# Brelok_MFU.net
KiCad netlist of a schematic drawn in Altium Designer
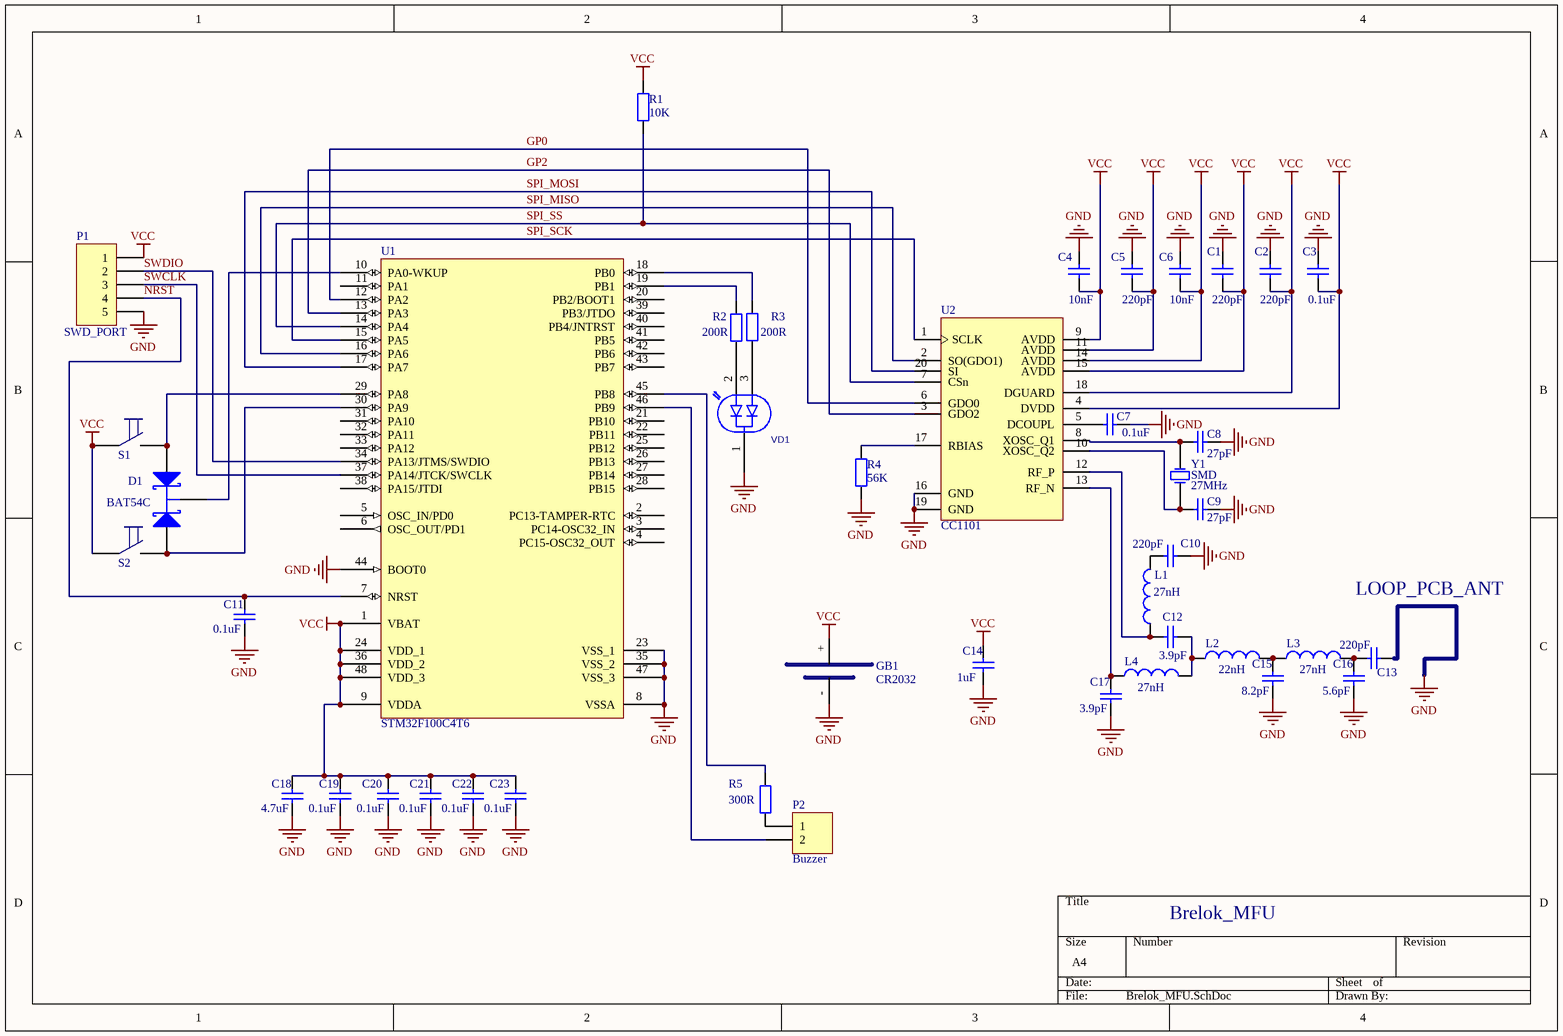
[diagram p0: Brelok_MFU.SchDoc]

(export (version "E")
  (design (tool "Eeschema 10.0.6"))
  (components
    (comp (ref "C1")
      (value "220pF")
      (footprint "C0603")
      (description "Capasitor_SMD_0808/")
      (fields (field (name "Comment") "0805"))
      (libsource (lib "NEW") (part "Capasitor_SMD_0805"))
    )
    (comp (ref "C2")
      (value "220pF")
      (footprint "C0603")
      (description "Capasitor_SMD_0808/")
      (fields (field (name "Comment") "0805"))
      (libsource (lib "NEW") (part "Capasitor_SMD_0805"))
    )
    (comp (ref "C3")
      (value "0.1uF")
      (footprint "C0603")
      (description "Capasitor_SMD_0808/")
      (fields (field (name "Comment") "0805"))
      (libsource (lib "NEW") (part "Capasitor_SMD_0805"))
    )
    (comp (ref "C4")
      (value "10nF")
      (footprint "C0603")
      (description "Capasitor_SMD_0808/")
      (fields (field (name "Comment") "0805"))
      (libsource (lib "NEW") (part "Capasitor_SMD_0805"))
    )
    (comp (ref "C5")
      (value "220pF")
      (footprint "C0603")
      (description "Capasitor_SMD_0808/")
      (fields (field (name "Comment") "0805"))
      (libsource (lib "NEW") (part "Capasitor_SMD_0805"))
    )
    (comp (ref "C6")
      (value "10nF")
      (footprint "C0603")
      (description "Capasitor_SMD_0808/")
      (fields (field (name "Comment") "0805"))
      (libsource (lib "NEW") (part "Capasitor_SMD_0805"))
    )
    (comp (ref "C7")
      (value "0.1uF")
      (footprint "C0603")
      (description "Capasitor_SMD_0808/")
      (fields (field (name "Comment") "0805"))
      (libsource (lib "NEW") (part "Capasitor_SMD_0805"))
    )
    (comp (ref "C8")
      (value "27pF")
      (footprint "C0603")
      (description "Capasitor_SMD_0808/")
      (fields (field (name "Comment") "0805"))
      (libsource (lib "NEW") (part "Capasitor_SMD_0805"))
    )
    (comp (ref "C9")
      (value "27pF")
      (footprint "C0603")
      (description "Capasitor_SMD_0808/")
      (fields (field (name "Comment") "0805"))
      (libsource (lib "NEW") (part "Capasitor_SMD_0805"))
    )
    (comp (ref "C10")
      (value "220pF")
      (footprint "C0603")
      (description "Capasitor_SMD_0808/")
      (fields (field (name "Comment") "0805"))
      (libsource (lib "NEW") (part "Capasitor_SMD_0805"))
    )
    (comp (ref "C11")
      (value "0.1uF")
      (footprint "C0603")
      (description "Capasitor_SMD_0808/")
      (fields (field (name "Comment") "0805"))
      (libsource (lib "NEW") (part "Capasitor_SMD_0805"))
    )
    (comp (ref "C12")
      (value "3.9pF")
      (footprint "C0603")
      (description "Capasitor_SMD_0808/")
      (fields (field (name "Comment") "0805"))
      (libsource (lib "NEW") (part "Capasitor_SMD_0805"))
    )
    (comp (ref "C13")
      (value "220pF")
      (footprint "C0603")
      (description "Capasitor_SMD_0808/")
      (fields (field (name "Comment") "0805"))
      (libsource (lib "NEW") (part "Capasitor_SMD_0805"))
    )
    (comp (ref "C14")
      (value "1uF")
      (footprint "C0603")
      (description "Capasitor_SMD_0808/")
      (fields (field (name "Comment") "0805"))
      (libsource (lib "NEW") (part "Capasitor_SMD_0805"))
    )
    (comp (ref "C15")
      (value "8.2pF")
      (footprint "C0603")
      (description "Capasitor_SMD_0808/")
      (fields (field (name "Comment") "0805"))
      (libsource (lib "NEW") (part "Capasitor_SMD_0805"))
    )
    (comp (ref "C16")
      (value "5.6pF")
      (footprint "C0603")
      (description "Capasitor_SMD_0808/")
      (fields (field (name "Comment") "0805"))
      (libsource (lib "NEW") (part "Capasitor_SMD_0805"))
    )
    (comp (ref "C17")
      (value "3.9pF")
      (footprint "C0603")
      (description "Capasitor_SMD_0808/")
      (fields (field (name "Comment") "0805"))
      (libsource (lib "NEW") (part "Capasitor_SMD_0805"))
    )
    (comp (ref "C18")
      (value "4.7uF")
      (footprint "C0805")
      (description "Capasitor_SMD_0808/")
      (fields (field (name "Comment") "0805"))
      (libsource (lib "NEW") (part "Capasitor_SMD_0805"))
    )
    (comp (ref "C19")
      (value "0.1uF")
      (footprint "C0603")
      (description "Capasitor_SMD_0808/")
      (fields (field (name "Comment") "0805"))
      (libsource (lib "NEW") (part "Capasitor_SMD_0805"))
    )
    (comp (ref "C20")
      (value "0.1uF")
      (footprint "C0603")
      (description "Capasitor_SMD_0808/")
      (fields (field (name "Comment") "0805"))
      (libsource (lib "NEW") (part "Capasitor_SMD_0805"))
    )
    (comp (ref "C21")
      (value "0.1uF")
      (footprint "C0603")
      (description "Capasitor_SMD_0808/")
      (fields (field (name "Comment") "0805"))
      (libsource (lib "NEW") (part "Capasitor_SMD_0805"))
    )
    (comp (ref "C22")
      (value "0.1uF")
      (footprint "C0603")
      (description "Capasitor_SMD_0808/")
      (fields (field (name "Comment") "0805"))
      (libsource (lib "NEW") (part "Capasitor_SMD_0805"))
    )
    (comp (ref "C23")
      (value "0.1uF")
      (footprint "C0603")
      (description "Capasitor_SMD_0808/")
      (fields (field (name "Comment") "0805"))
      (libsource (lib "NEW") (part "Capasitor_SMD_0805"))
    )
    (comp (ref "D1")
      (value "BAT54C")
      (footprint "SOT23_N")
      (description "Schottky Barrier Double Diode")
      (fields (field (name "PUBLISHER") "Altium Limited"))
      (libsource (lib "Philips Discrete Diode - Schottky") (part "BAT54C"))
    )
    (comp (ref "GB1")
      (value "CR2032")
      (footprint "BAT_Holder_CR2032")
      (description "BTH-W39-20")
      (libsource (lib "NEW") (part "BAT_Holder_CR2032"))
    )
    (comp (ref "L1")
      (value "27nH")
      (footprint "L0603")
      (fields (field (name "Comment") "SMD"))
      (libsource (lib "NEW") (part "Induktor_SMD"))
    )
    (comp (ref "L2")
      (value "22nH")
      (footprint "L0603")
      (fields (field (name "Comment") "SMD"))
      (libsource (lib "NEW") (part "Induktor_SMD"))
    )
    (comp (ref "L3")
      (value "27nH")
      (footprint "L0603")
      (fields (field (name "Comment") "SMD"))
      (libsource (lib "NEW") (part "Induktor_SMD"))
    )
    (comp (ref "L4")
      (value "27nH")
      (footprint "L0603")
      (fields (field (name "Comment") "SMD"))
      (libsource (lib "NEW") (part "Induktor_SMD"))
    )
    (comp (ref "P1")
      (value "SWD_PORT")
      (footprint "HDR1X5")
      (description "Header, 5-Pin")
      (fields (field (name "PUBLISHER") "Altium Limited"))
      (libsource (lib "Miscellaneous Connectors") (part "Header 5"))
    )
    (comp (ref "P2")
      (value "Buzzer")
      (footprint "HDR1X2")
      (description "Header, 2-Pin")
      (fields (field (name "PUBLISHER") "Altium Limited"))
      (libsource (lib "Miscellaneous Connectors") (part "Header 2"))
    )
    (comp (ref "R1")
      (value "10K")
      (footprint "C0603")
      (description "Resistor")
      (fields (field (name "Comment") "RES"))
      (libsource (lib "NEW") (part "RES"))
    )
    (comp (ref "R2")
      (value "200R")
      (footprint "C0603")
      (description "Resistor")
      (fields (field (name "Comment") "RES"))
      (libsource (lib "NEW") (part "RES"))
    )
    (comp (ref "R3")
      (value "200R")
      (footprint "C0603")
      (description "Resistor")
      (fields (field (name "Comment") "RES"))
      (libsource (lib "NEW") (part "RES"))
    )
    (comp (ref "R4")
      (value "56K")
      (footprint "C0603")
      (description "Resistor")
      (fields (field (name "Comment") "RES"))
      (libsource (lib "NEW") (part "RES"))
    )
    (comp (ref "R5")
      (value "300R")
      (footprint "C0603")
      (description "Resistor")
      (fields (field (name "Comment") "RES"))
      (libsource (lib "NEW") (part "RES"))
    )
    (comp (ref "S1")
      (value "KAN0642-0501B")
      (footprint "KAN0642-0501B")
      (libsource (lib "NEW") (part "KAN0642-0501B"))
    )
    (comp (ref "S2")
      (value "KAN0642-0501B")
      (footprint "KAN0642-0501B")
      (libsource (lib "NEW") (part "KAN0642-0501B"))
    )
    (comp (ref "U1")
      (value "STM32F100C4T6")
      (footprint "LQFP48_M")
      (description "STM32 ARM-based 32-bit MCU with 32 Kbytes Flash, 48-pin LQFP, Industrial Temperature")
      (fields (field (name "PUBLISHER") "Altium Limited"))
      (libsource (lib "ST Microcontroller 32-Bit STM32") (part "STM32F101C6T6"))
    )
    (comp (ref "U2") (value "CC1101") (footprint "VQFN20") (libsource (lib "NEW") (part "CC1101")))
    (comp (ref "VD1")
      (value "LIGHTDIODE2")
      (footprint "LIGHTDIODE2")
      (libsource (lib "NEW") (part "LIGHTDIODE2"))
    )
    (comp (ref "Y1")
      (value "SMD")
      (footprint "Quartz_SMD0603")
      (fields (field (name "ALTIUM_UNNAMED_1") "27MHz"))
      (libsource (lib "NEW") (part "Quartz_SMD"))
    )
  )
  (nets
    (net (code "1") (name "/GP0") (class "Default")
      (node (ref "U1") (pin "12") (pinfunction "PA2_12") (pintype "bidirectional"))
      (node (ref "U2") (pin "6") (pinfunction "GDO0_6") (pintype "passive"))
    )
    (net (code "2") (name "/GP2") (class "Default")
      (node (ref "U1") (pin "13") (pinfunction "PA3_13") (pintype "bidirectional"))
      (node (ref "U2") (pin "3") (pinfunction "GDO2_3") (pintype "passive"))
    )
    (net (code "3") (name "/NRST") (class "Default")
      (node (ref "C11") (pin "1") (pinfunction "1_1") (pintype "passive"))
      (node (ref "P1") (pin "4") (pinfunction "4_4") (pintype "passive"))
      (node (ref "U1") (pin "7") (pinfunction "NRST_7") (pintype "bidirectional"))
    )
    (net (code "4") (name "/SPI_MISO") (class "Default")
      (node (ref "U1") (pin "16") (pinfunction "PA6_16") (pintype "bidirectional"))
      (node (ref "U2") (pin "2") (pinfunction "SO(GDO1)_2") (pintype "passive"))
    )
    (net (code "5") (name "/SPI_MOSI") (class "Default")
      (node (ref "U1") (pin "17") (pinfunction "PA7_17") (pintype "bidirectional"))
      (node (ref "U2") (pin "20") (pinfunction "SI_20") (pintype "passive"))
    )
    (net (code "6") (name "/SPI_SCK") (class "Default")
      (node (ref "U1") (pin "15") (pinfunction "PA5_15") (pintype "bidirectional"))
      (node (ref "U2") (pin "1") (pinfunction "SCLK_1") (pintype "passive"))
    )
    (net (code "7") (name "/SPI_SS") (class "Default")
      (node (ref "R1") (pin "1") (pinfunction "1_1") (pintype "passive"))
      (node (ref "U1") (pin "14") (pinfunction "PA4_14") (pintype "bidirectional"))
      (node (ref "U2") (pin "7") (pinfunction "CSn_7") (pintype "passive"))
    )
    (net (code "8") (name "/SWCLK") (class "Default")
      (node (ref "P1") (pin "3") (pinfunction "3_3") (pintype "passive"))
      (node (ref "U1") (pin "37") (pinfunction "PA14/JTCK/SWCLK_37") (pintype "bidirectional"))
    )
    (net (code "9") (name "/SWDIO") (class "Default")
      (node (ref "P1") (pin "2") (pinfunction "2_2") (pintype "passive"))
      (node (ref "U1") (pin "34") (pinfunction "PA13/JTMS/SWDIO_34") (pintype "bidirectional"))
    )
    (net (code "10") (name "GND") (class "Default")
      (node (ref "C1") (pin "1") (pinfunction "1_1") (pintype "passive"))
      (node (ref "C10") (pin "2") (pinfunction "2_2") (pintype "passive"))
      (node (ref "C11") (pin "2") (pinfunction "2_2") (pintype "passive"))
      (node (ref "C13") (pin "2") (pinfunction "2_2") (pintype "passive"))
      (node (ref "C14") (pin "2") (pinfunction "2_2") (pintype "passive"))
      (node (ref "C15") (pin "1") (pinfunction "1_1") (pintype "passive"))
      (node (ref "C16") (pin "1") (pinfunction "1_1") (pintype "passive"))
      (node (ref "C17") (pin "1") (pinfunction "1_1") (pintype "passive"))
      (node (ref "C18") (pin "2") (pinfunction "2_2") (pintype "passive"))
      (node (ref "C19") (pin "2") (pinfunction "2_2") (pintype "passive"))
      (node (ref "C2") (pin "1") (pinfunction "1_1") (pintype "passive"))
      (node (ref "C20") (pin "2") (pinfunction "2_2") (pintype "passive"))
      (node (ref "C21") (pin "2") (pinfunction "2_2") (pintype "passive"))
      (node (ref "C22") (pin "2") (pinfunction "2_2") (pintype "passive"))
      (node (ref "C23") (pin "2") (pinfunction "2_2") (pintype "passive"))
      (node (ref "C3") (pin "1") (pinfunction "1_1") (pintype "passive"))
      (node (ref "C4") (pin "1") (pinfunction "1_1") (pintype "passive"))
      (node (ref "C5") (pin "1") (pinfunction "1_1") (pintype "passive"))
      (node (ref "C6") (pin "1") (pinfunction "1_1") (pintype "passive"))
      (node (ref "C7") (pin "2") (pinfunction "2_2") (pintype "passive"))
      (node (ref "C8") (pin "2") (pinfunction "2_2") (pintype "passive"))
      (node (ref "C9") (pin "2") (pinfunction "2_2") (pintype "passive"))
      (node (ref "GB1") (pin "-") (pinfunction "-_-") (pintype "passive"))
      (node (ref "P1") (pin "5") (pinfunction "5_5") (pintype "passive"))
      (node (ref "R4") (pin "1") (pinfunction "1_1") (pintype "passive"))
      (node (ref "U1") (pin "23") (pinfunction "VSS_1_23") (pintype "power_in"))
      (node (ref "U1") (pin "35") (pinfunction "VSS_2_35") (pintype "power_in"))
      (node (ref "U1") (pin "44") (pinfunction "BOOT0_44") (pintype "input"))
      (node (ref "U1") (pin "47") (pinfunction "VSS_3_47") (pintype "power_in"))
      (node (ref "U1") (pin "8") (pinfunction "VSSA_8") (pintype "power_in"))
      (node (ref "U2") (pin "16") (pinfunction "GND_16") (pintype "passive"))
      (node (ref "U2") (pin "19") (pinfunction "GND_19") (pintype "passive"))
      (node (ref "VD1") (pin "1") (pintype "passive"))
    )
    (net (code "11") (name "Net-(C10-Pad1)") (class "Default")
      (node (ref "C10") (pin "1") (pinfunction "1_1") (pintype "passive"))
      (node (ref "L1") (pin "2") (pinfunction "2_2") (pintype "passive"))
    )
    (net (code "12") (name "Net-(C12-Pad1)") (class "Default")
      (node (ref "C12") (pin "1") (pinfunction "1_1") (pintype "passive"))
      (node (ref "L2") (pin "1") (pinfunction "1_1") (pintype "passive"))
      (node (ref "L4") (pin "2") (pinfunction "2_2") (pintype "passive"))
    )
    (net (code "13") (name "Net-(C13-Pad1)") (class "Default")
      (node (ref "C13") (pin "1") (pinfunction "1_1") (pintype "passive"))
      (node (ref "C16") (pin "2") (pinfunction "2_2") (pintype "passive"))
      (node (ref "L3") (pin "2") (pinfunction "2_2") (pintype "passive"))
    )
    (net (code "14") (name "Net-(C15-Pad2)") (class "Default")
      (node (ref "C15") (pin "2") (pinfunction "2_2") (pintype "passive"))
      (node (ref "L2") (pin "2") (pinfunction "2_2") (pintype "passive"))
      (node (ref "L3") (pin "1") (pinfunction "1_1") (pintype "passive"))
    )
    (net (code "15") (name "Net-(D1-A1)") (class "Default")
      (node (ref "D1") (pin "1") (pinfunction "A1_1") (pintype "passive"))
      (node (ref "S1") (pin "2") (pinfunction "2_2") (pintype "passive"))
      (node (ref "U1") (pin "29") (pinfunction "PA8_29") (pintype "bidirectional"))
    )
    (net (code "16") (name "Net-(D1-A2)") (class "Default")
      (node (ref "D1") (pin "2") (pinfunction "A2_2") (pintype "passive"))
      (node (ref "S2") (pin "2") (pinfunction "2_2") (pintype "passive"))
      (node (ref "U1") (pin "30") (pinfunction "PA9_30") (pintype "bidirectional"))
    )
    (net (code "17") (name "Net-(D1-K)") (class "Default")
      (node (ref "D1") (pin "3") (pinfunction "K_3") (pintype "passive"))
      (node (ref "U1") (pin "10") (pinfunction "PA0-WKUP_10") (pintype "bidirectional"))
    )
    (net (code "18") (name "Net-(P2-Pad1)") (class "Default")
      (node (ref "P2") (pin "1") (pinfunction "1_1") (pintype "passive"))
      (node (ref "R5") (pin "1") (pinfunction "1_1") (pintype "passive"))
    )
    (net (code "19") (name "Net-(R2-Pad1)") (class "Default")
      (node (ref "R2") (pin "1") (pinfunction "1_1") (pintype "passive"))
      (node (ref "VD1") (pin "2") (pintype "passive"))
    )
    (net (code "20") (name "Net-(R3-Pad1)") (class "Default")
      (node (ref "R3") (pin "1") (pinfunction "1_1") (pintype "passive"))
      (node (ref "VD1") (pin "3") (pintype "passive"))
    )
    (net (code "21") (name "Net-(U1-PB0)") (class "Default")
      (node (ref "R3") (pin "2") (pinfunction "2_2") (pintype "passive"))
      (node (ref "U1") (pin "18") (pinfunction "PB0_18") (pintype "bidirectional"))
    )
    (net (code "22") (name "Net-(U1-PB1)") (class "Default")
      (node (ref "R2") (pin "2") (pinfunction "2_2") (pintype "passive"))
      (node (ref "U1") (pin "19") (pinfunction "PB1_19") (pintype "bidirectional"))
    )
    (net (code "23") (name "Net-(U1-PB8)") (class "Default")
      (node (ref "R5") (pin "2") (pinfunction "2_2") (pintype "passive"))
      (node (ref "U1") (pin "45") (pinfunction "PB8_45") (pintype "bidirectional"))
    )
    (net (code "24") (name "Net-(U1-PB9)") (class "Default")
      (node (ref "P2") (pin "2") (pinfunction "2_2") (pintype "passive"))
      (node (ref "U1") (pin "46") (pinfunction "PB9_46") (pintype "bidirectional"))
    )
    (net (code "25") (name "Net-(U2-DCOUPL)") (class "Default")
      (node (ref "C7") (pin "1") (pinfunction "1_1") (pintype "passive"))
      (node (ref "U2") (pin "5") (pinfunction "DCOUPL_5") (pintype "passive"))
    )
    (net (code "26") (name "Net-(U2-RBIAS)") (class "Default")
      (node (ref "R4") (pin "2") (pinfunction "2_2") (pintype "passive"))
      (node (ref "U2") (pin "17") (pinfunction "RBIAS_17") (pintype "passive"))
    )
    (net (code "27") (name "Net-(U2-RF_N)") (class "Default")
      (node (ref "C17") (pin "2") (pinfunction "2_2") (pintype "passive"))
      (node (ref "L4") (pin "1") (pinfunction "1_1") (pintype "passive"))
      (node (ref "U2") (pin "13") (pinfunction "RF_N_13") (pintype "passive"))
    )
    (net (code "28") (name "Net-(U2-RF_P)") (class "Default")
      (node (ref "C12") (pin "2") (pinfunction "2_2") (pintype "passive"))
      (node (ref "L1") (pin "1") (pinfunction "1_1") (pintype "passive"))
      (node (ref "U2") (pin "12") (pinfunction "RF_P_12") (pintype "passive"))
    )
    (net (code "29") (name "Net-(U2-XOSC_Q1)") (class "Default")
      (node (ref "C8") (pin "1") (pinfunction "1_1") (pintype "passive"))
      (node (ref "U2") (pin "8") (pinfunction "XOSC_Q1_8") (pintype "passive"))
      (node (ref "Y1") (pin "1") (pinfunction "OSC1_1") (pintype "passive"))
    )
    (net (code "30") (name "Net-(U2-XOSC_Q2)") (class "Default")
      (node (ref "C9") (pin "1") (pinfunction "1_1") (pintype "passive"))
      (node (ref "U2") (pin "10") (pinfunction "XOSC_Q2_10") (pintype "passive"))
      (node (ref "Y1") (pin "3") (pinfunction "OSC2_3") (pintype "passive"))
    )
    (net (code "31") (name "VCC") (class "Default")
      (node (ref "C1") (pin "2") (pinfunction "2_2") (pintype "passive"))
      (node (ref "C14") (pin "1") (pinfunction "1_1") (pintype "passive"))
      (node (ref "C18") (pin "1") (pinfunction "1_1") (pintype "passive"))
      (node (ref "C19") (pin "1") (pinfunction "1_1") (pintype "passive"))
      (node (ref "C2") (pin "2") (pinfunction "2_2") (pintype "passive"))
      (node (ref "C20") (pin "1") (pinfunction "1_1") (pintype "passive"))
      (node (ref "C21") (pin "1") (pinfunction "1_1") (pintype "passive"))
      (node (ref "C22") (pin "1") (pinfunction "1_1") (pintype "passive"))
      (node (ref "C23") (pin "1") (pinfunction "1_1") (pintype "passive"))
      (node (ref "C3") (pin "2") (pinfunction "2_2") (pintype "passive"))
      (node (ref "C4") (pin "2") (pinfunction "2_2") (pintype "passive"))
      (node (ref "C5") (pin "2") (pinfunction "2_2") (pintype "passive"))
      (node (ref "C6") (pin "2") (pinfunction "2_2") (pintype "passive"))
      (node (ref "GB1") (pin "+") (pinfunction "+_+") (pintype "passive"))
      (node (ref "P1") (pin "1") (pinfunction "1_1") (pintype "passive"))
      (node (ref "R1") (pin "2") (pinfunction "2_2") (pintype "passive"))
      (node (ref "S1") (pin "1") (pinfunction "1_1") (pintype "passive"))
      (node (ref "S2") (pin "1") (pinfunction "1_1") (pintype "passive"))
      (node (ref "U1") (pin "1") (pinfunction "VBAT_1") (pintype "power_in"))
      (node (ref "U1") (pin "24") (pinfunction "VDD_1_24") (pintype "power_in"))
      (node (ref "U1") (pin "36") (pinfunction "VDD_2_36") (pintype "power_in"))
      (node (ref "U1") (pin "48") (pinfunction "VDD_3_48") (pintype "power_in"))
      (node (ref "U1") (pin "9") (pinfunction "VDDA_9") (pintype "power_in"))
      (node (ref "U2") (pin "11") (pinfunction "AVDD_11") (pintype "passive"))
      (node (ref "U2") (pin "14") (pinfunction "AVDD_14") (pintype "passive"))
      (node (ref "U2") (pin "15") (pinfunction "AVDD_15") (pintype "passive"))
      (node (ref "U2") (pin "18") (pinfunction "DGUARD_18") (pintype "passive"))
      (node (ref "U2") (pin "4") (pinfunction "DVDD_4") (pintype "passive"))
      (node (ref "U2") (pin "9") (pinfunction "AVDD_9") (pintype "passive"))
    )
    (net (code "32") (name "unconnected-(U1-OSC_IN{slash}PD0-Pad5)") (class "Default")
      (node (ref "U1") (pin "5") (pinfunction "OSC_IN/PD0_5") (pintype "input"))
    )
    (net (code "33") (name "unconnected-(U1-OSC_OUT{slash}PD1-Pad6)") (class "Default")
      (node (ref "U1") (pin "6") (pinfunction "OSC_OUT/PD1_6") (pintype "output"))
    )
    (net (code "34") (name "unconnected-(U1-PA1-Pad11)") (class "Default")
      (node (ref "U1") (pin "11") (pinfunction "PA1_11") (pintype "bidirectional"))
    )
    (net (code "35") (name "unconnected-(U1-PA10-Pad31)") (class "Default")
      (node (ref "U1") (pin "31") (pinfunction "PA10_31") (pintype "bidirectional"))
    )
    (net (code "36") (name "unconnected-(U1-PA11-Pad32)") (class "Default")
      (node (ref "U1") (pin "32") (pinfunction "PA11_32") (pintype "bidirectional"))
    )
    (net (code "37") (name "unconnected-(U1-PA12-Pad33)") (class "Default")
      (node (ref "U1") (pin "33") (pinfunction "PA12_33") (pintype "bidirectional"))
    )
    (net (code "38") (name "unconnected-(U1-PA15{slash}JTDI-Pad38)") (class "Default")
      (node (ref "U1") (pin "38") (pinfunction "PA15/JTDI_38") (pintype "bidirectional"))
    )
    (net (code "39") (name "unconnected-(U1-PB2{slash}BOOT1-Pad20)") (class "Default")
      (node (ref "U1") (pin "20") (pinfunction "PB2/BOOT1_20") (pintype "bidirectional"))
    )
    (net (code "40") (name "unconnected-(U1-PB3{slash}JTDO-Pad39)") (class "Default")
      (node (ref "U1") (pin "39") (pinfunction "PB3/JTDO_39") (pintype "bidirectional"))
    )
    (net (code "41") (name "unconnected-(U1-PB4{slash}JNTRST-Pad40)") (class "Default")
      (node (ref "U1") (pin "40") (pinfunction "PB4/JNTRST_40") (pintype "bidirectional"))
    )
    (net (code "42") (name "unconnected-(U1-PB5-Pad41)") (class "Default")
      (node (ref "U1") (pin "41") (pinfunction "PB5_41") (pintype "bidirectional"))
    )
    (net (code "43") (name "unconnected-(U1-PB6-Pad42)") (class "Default")
      (node (ref "U1") (pin "42") (pinfunction "PB6_42") (pintype "bidirectional"))
    )
    (net (code "44") (name "unconnected-(U1-PB7-Pad43)") (class "Default")
      (node (ref "U1") (pin "43") (pinfunction "PB7_43") (pintype "bidirectional"))
    )
    (net (code "45") (name "unconnected-(U1-PB10-Pad21)") (class "Default")
      (node (ref "U1") (pin "21") (pinfunction "PB10_21") (pintype "bidirectional"))
    )
    (net (code "46") (name "unconnected-(U1-PB11-Pad22)") (class "Default")
      (node (ref "U1") (pin "22") (pinfunction "PB11_22") (pintype "bidirectional"))
    )
    (net (code "47") (name "unconnected-(U1-PB12-Pad25)") (class "Default")
      (node (ref "U1") (pin "25") (pinfunction "PB12_25") (pintype "bidirectional"))
    )
    (net (code "48") (name "unconnected-(U1-PB13-Pad26)") (class "Default")
      (node (ref "U1") (pin "26") (pinfunction "PB13_26") (pintype "bidirectional"))
    )
    (net (code "49") (name "unconnected-(U1-PB14-Pad27)") (class "Default")
      (node (ref "U1") (pin "27") (pinfunction "PB14_27") (pintype "bidirectional"))
    )
    (net (code "50") (name "unconnected-(U1-PB15-Pad28)") (class "Default")
      (node (ref "U1") (pin "28") (pinfunction "PB15_28") (pintype "bidirectional"))
    )
    (net (code "51") (name "unconnected-(U1-PC13-TAMPER-RTC-Pad2)") (class "Default")
      (node (ref "U1") (pin "2") (pinfunction "PC13-TAMPER-RTC_2") (pintype "bidirectional"))
    )
    (net (code "52") (name "unconnected-(U1-PC14-OSC32_IN-Pad3)") (class "Default")
      (node (ref "U1") (pin "3") (pinfunction "PC14-OSC32_IN_3") (pintype "bidirectional"))
    )
    (net (code "53") (name "unconnected-(U1-PC15-OSC32_OUT-Pad4)") (class "Default")
      (node (ref "U1") (pin "4") (pinfunction "PC15-OSC32_OUT_4") (pintype "bidirectional"))
    )
  )
)
